# 1-Schematic_1-Optimised-IRT-Gr4-ColleJou.net
KiCad netlist of a schematic drawn in EasyEDA
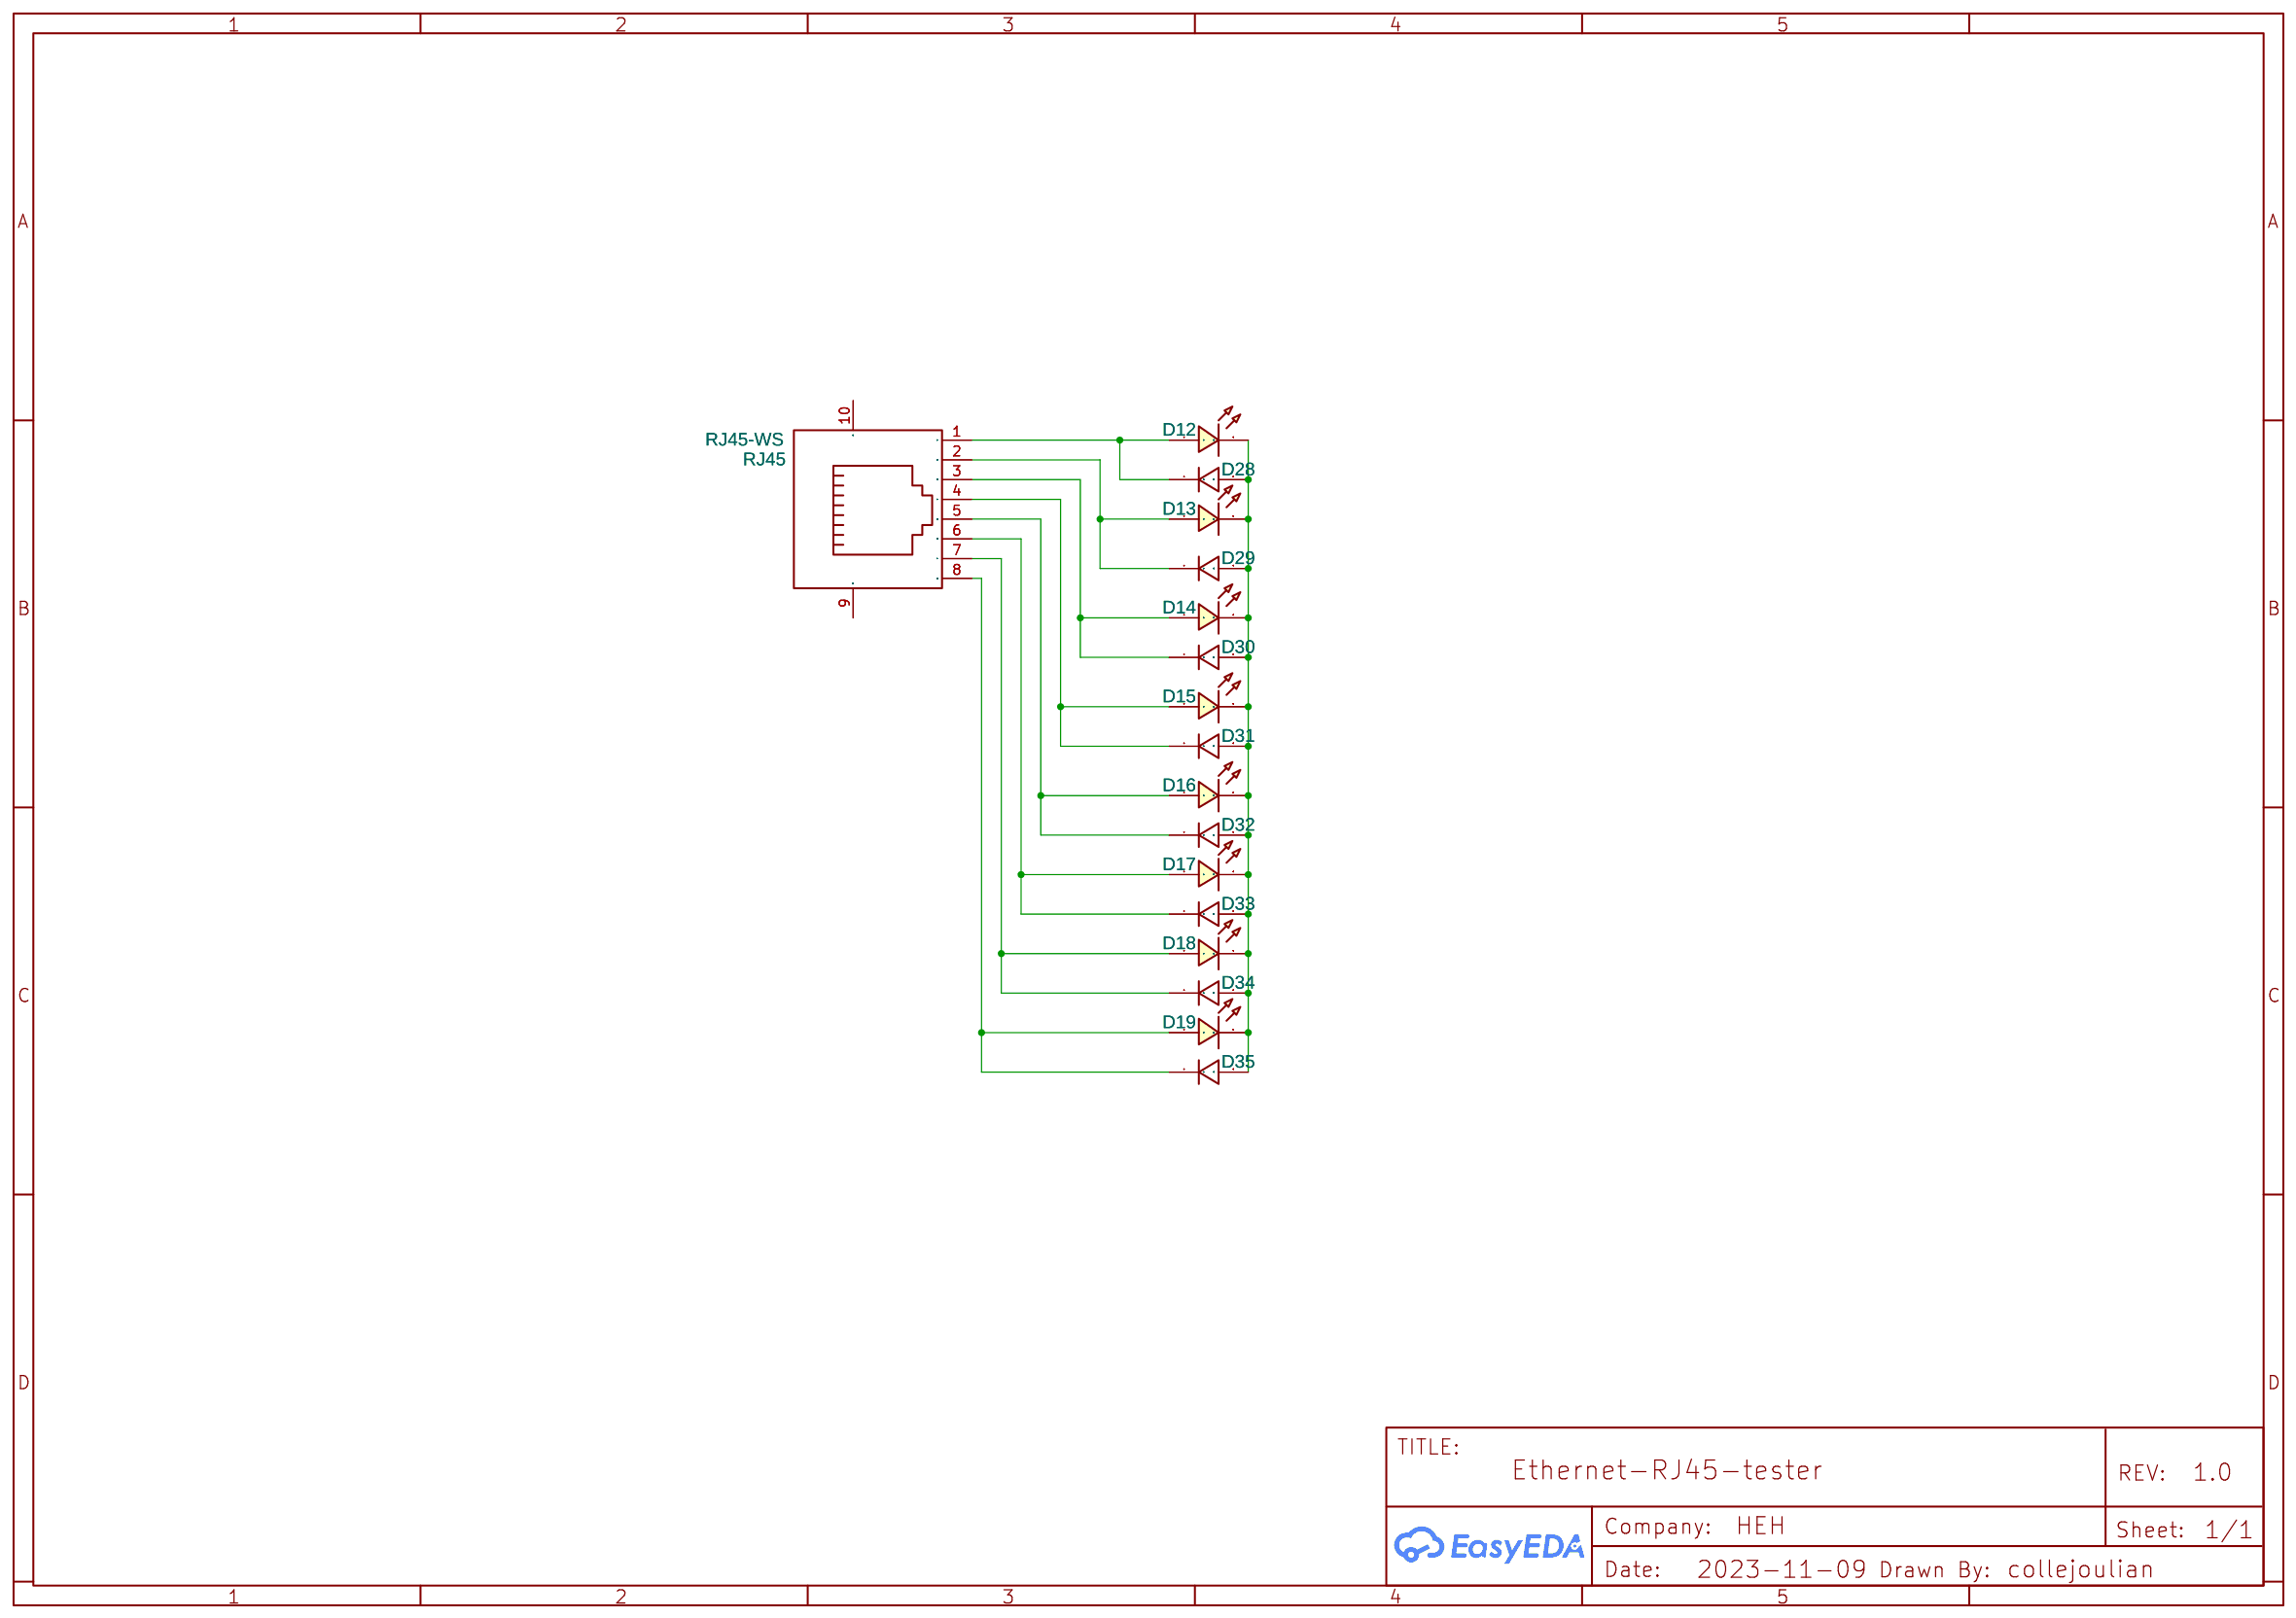
[diagram p0: schematic sheet]

(export (version "E")
  (design (tool "Eeschema 10.0.6"))
  (components
    (comp (ref "D12")
      (value "D12")
      (fields
        (field (name "Manufacturer Part") "204-10SDRD/S530-A3-L")
        (field (name "Manufacturer") "EVERLIGHT(台湾亿光)")
      )
      (libsource (lib "") (part "LED-TH-3mm_R"))
    )
    (comp (ref "D13")
      (value "D13")
      (fields
        (field (name "Manufacturer Part") "204-10SDRD/S530-A3-L")
        (field (name "Manufacturer") "EVERLIGHT(台湾亿光)")
      )
      (libsource (lib "") (part "LED-TH-3mm_R"))
    )
    (comp (ref "D14")
      (value "D14")
      (fields
        (field (name "Manufacturer Part") "204-10SDRD/S530-A3-L")
        (field (name "Manufacturer") "EVERLIGHT(台湾亿光)")
      )
      (libsource (lib "") (part "LED-TH-3mm_R"))
    )
    (comp (ref "D15")
      (value "D15")
      (fields
        (field (name "Manufacturer Part") "204-10SDRD/S530-A3-L")
        (field (name "Manufacturer") "EVERLIGHT(台湾亿光)")
      )
      (libsource (lib "") (part "LED-TH-3mm_R"))
    )
    (comp (ref "D16")
      (value "D16")
      (fields
        (field (name "Manufacturer Part") "204-10SDRD/S530-A3-L")
        (field (name "Manufacturer") "EVERLIGHT(台湾亿光)")
      )
      (libsource (lib "") (part "LED-TH-3mm_R"))
    )
    (comp (ref "D17")
      (value "D17")
      (fields
        (field (name "Manufacturer Part") "204-10SDRD/S530-A3-L")
        (field (name "Manufacturer") "EVERLIGHT(台湾亿光)")
      )
      (libsource (lib "") (part "LED-TH-3mm_R"))
    )
    (comp (ref "D18")
      (value "D18")
      (fields
        (field (name "Manufacturer Part") "204-10SDRD/S530-A3-L")
        (field (name "Manufacturer") "EVERLIGHT(台湾亿光)")
      )
      (libsource (lib "") (part "LED-TH-3mm_R"))
    )
    (comp (ref "D19")
      (value "D19")
      (fields
        (field (name "Manufacturer Part") "204-10SDRD/S530-A3-L")
        (field (name "Manufacturer") "EVERLIGHT(台湾亿光)")
      )
      (libsource (lib "") (part "LED-TH-3mm_R"))
    )
    (comp (ref "D28")
      (value "D28")
      (fields (field (name "Manufacturer Part") "1N4148") (field (name "Manufacturer") "STMicroelectronics"))
      (libsource (lib "") (part "1N4148"))
    )
    (comp (ref "D29")
      (value "D29")
      (fields (field (name "Manufacturer Part") "1N4148") (field (name "Manufacturer") "STMicroelectronics"))
      (libsource (lib "") (part "1N4148"))
    )
    (comp (ref "D30")
      (value "D30")
      (fields (field (name "Manufacturer Part") "1N4148") (field (name "Manufacturer") "STMicroelectronics"))
      (libsource (lib "") (part "1N4148"))
    )
    (comp (ref "D31")
      (value "D31")
      (fields (field (name "Manufacturer Part") "1N4148") (field (name "Manufacturer") "STMicroelectronics"))
      (libsource (lib "") (part "1N4148"))
    )
    (comp (ref "D32")
      (value "D32")
      (fields (field (name "Manufacturer Part") "1N4148") (field (name "Manufacturer") "STMicroelectronics"))
      (libsource (lib "") (part "1N4148"))
    )
    (comp (ref "D33")
      (value "D33")
      (fields (field (name "Manufacturer Part") "1N4148") (field (name "Manufacturer") "STMicroelectronics"))
      (libsource (lib "") (part "1N4148"))
    )
    (comp (ref "D34")
      (value "D34")
      (fields (field (name "Manufacturer Part") "1N4148") (field (name "Manufacturer") "STMicroelectronics"))
      (libsource (lib "") (part "1N4148"))
    )
    (comp (ref "D35")
      (value "D35")
      (fields (field (name "Manufacturer Part") "1N4148") (field (name "Manufacturer") "STMicroelectronics"))
      (libsource (lib "") (part "1N4148"))
    )
    (comp (ref "RJ45")
      (value "RJ45-WS")
      (fields
        (field (name "Manufacturer Part") "FRJ45004-1100K6K02C0")
        (field (name "Manufacturer") "TXGA(特思嘉)")
      )
      (libsource (lib "") (part "FRJ45004-1100K6K02C0"))
    )
  )
  (nets
    (net (code "1") (name "Net-(D12-Pad1)") (class "Default")
      (node (ref "D12") (pin "1") (pinfunction "1_1") (pintype "unspecified"))
      (node (ref "D28") (pin "1") (pinfunction "1_1") (pintype "unspecified"))
      (node (ref "RJ45") (pin "1") (pinfunction "1_1") (pintype "unspecified"))
    )
    (net (code "2") (name "Net-(D12-Pad2)") (class "Default")
      (node (ref "D12") (pin "2") (pinfunction "2_2") (pintype "unspecified"))
      (node (ref "D13") (pin "2") (pinfunction "2_2") (pintype "unspecified"))
      (node (ref "D14") (pin "2") (pinfunction "2_2") (pintype "unspecified"))
      (node (ref "D15") (pin "2") (pinfunction "2_2") (pintype "unspecified"))
      (node (ref "D16") (pin "2") (pinfunction "2_2") (pintype "unspecified"))
      (node (ref "D17") (pin "2") (pinfunction "2_2") (pintype "unspecified"))
      (node (ref "D18") (pin "2") (pinfunction "2_2") (pintype "unspecified"))
      (node (ref "D19") (pin "2") (pinfunction "2_2") (pintype "unspecified"))
      (node (ref "D28") (pin "2") (pinfunction "2_2") (pintype "unspecified"))
      (node (ref "D29") (pin "2") (pinfunction "2_2") (pintype "unspecified"))
      (node (ref "D30") (pin "2") (pinfunction "2_2") (pintype "unspecified"))
      (node (ref "D31") (pin "2") (pinfunction "2_2") (pintype "unspecified"))
      (node (ref "D32") (pin "2") (pinfunction "2_2") (pintype "unspecified"))
      (node (ref "D33") (pin "2") (pinfunction "2_2") (pintype "unspecified"))
      (node (ref "D34") (pin "2") (pinfunction "2_2") (pintype "unspecified"))
      (node (ref "D35") (pin "2") (pinfunction "2_2") (pintype "unspecified"))
    )
    (net (code "3") (name "Net-(D13-Pad1)") (class "Default")
      (node (ref "D13") (pin "1") (pinfunction "1_1") (pintype "unspecified"))
      (node (ref "D29") (pin "1") (pinfunction "1_1") (pintype "unspecified"))
      (node (ref "RJ45") (pin "2") (pinfunction "2_2") (pintype "unspecified"))
    )
    (net (code "4") (name "Net-(D14-Pad1)") (class "Default")
      (node (ref "D14") (pin "1") (pinfunction "1_1") (pintype "unspecified"))
      (node (ref "D30") (pin "1") (pinfunction "1_1") (pintype "unspecified"))
      (node (ref "RJ45") (pin "3") (pinfunction "3_3") (pintype "unspecified"))
    )
    (net (code "5") (name "Net-(D15-Pad1)") (class "Default")
      (node (ref "D15") (pin "1") (pinfunction "1_1") (pintype "unspecified"))
      (node (ref "D31") (pin "1") (pinfunction "1_1") (pintype "unspecified"))
      (node (ref "RJ45") (pin "4") (pinfunction "4_4") (pintype "unspecified"))
    )
    (net (code "6") (name "Net-(D16-Pad1)") (class "Default")
      (node (ref "D16") (pin "1") (pinfunction "1_1") (pintype "unspecified"))
      (node (ref "D32") (pin "1") (pinfunction "1_1") (pintype "unspecified"))
      (node (ref "RJ45") (pin "5") (pinfunction "5_5") (pintype "unspecified"))
    )
    (net (code "7") (name "Net-(D17-Pad1)") (class "Default")
      (node (ref "D17") (pin "1") (pinfunction "1_1") (pintype "unspecified"))
      (node (ref "D33") (pin "1") (pinfunction "1_1") (pintype "unspecified"))
      (node (ref "RJ45") (pin "6") (pinfunction "6_6") (pintype "unspecified"))
    )
    (net (code "8") (name "Net-(D18-Pad1)") (class "Default")
      (node (ref "D18") (pin "1") (pinfunction "1_1") (pintype "unspecified"))
      (node (ref "D34") (pin "1") (pinfunction "1_1") (pintype "unspecified"))
      (node (ref "RJ45") (pin "7") (pinfunction "7_7") (pintype "unspecified"))
    )
    (net (code "9") (name "Net-(D19-Pad1)") (class "Default")
      (node (ref "D19") (pin "1") (pinfunction "1_1") (pintype "unspecified"))
      (node (ref "D35") (pin "1") (pinfunction "1_1") (pintype "unspecified"))
      (node (ref "RJ45") (pin "8") (pinfunction "8_8") (pintype "unspecified"))
    )
    (net (code "10") (name "unconnected-(RJ45-EH-Pad9)") (class "Default")
      (node (ref "RJ45") (pin "9") (pinfunction "EH_9") (pintype "unspecified"))
    )
    (net (code "11") (name "unconnected-(RJ45-EH-Pad10)") (class "Default")
      (node (ref "RJ45") (pin "10") (pinfunction "EH_10") (pintype "unspecified"))
    )
  )
)
